# USTREDNA.net
KiCad netlist of a schematic drawn in EAGLE
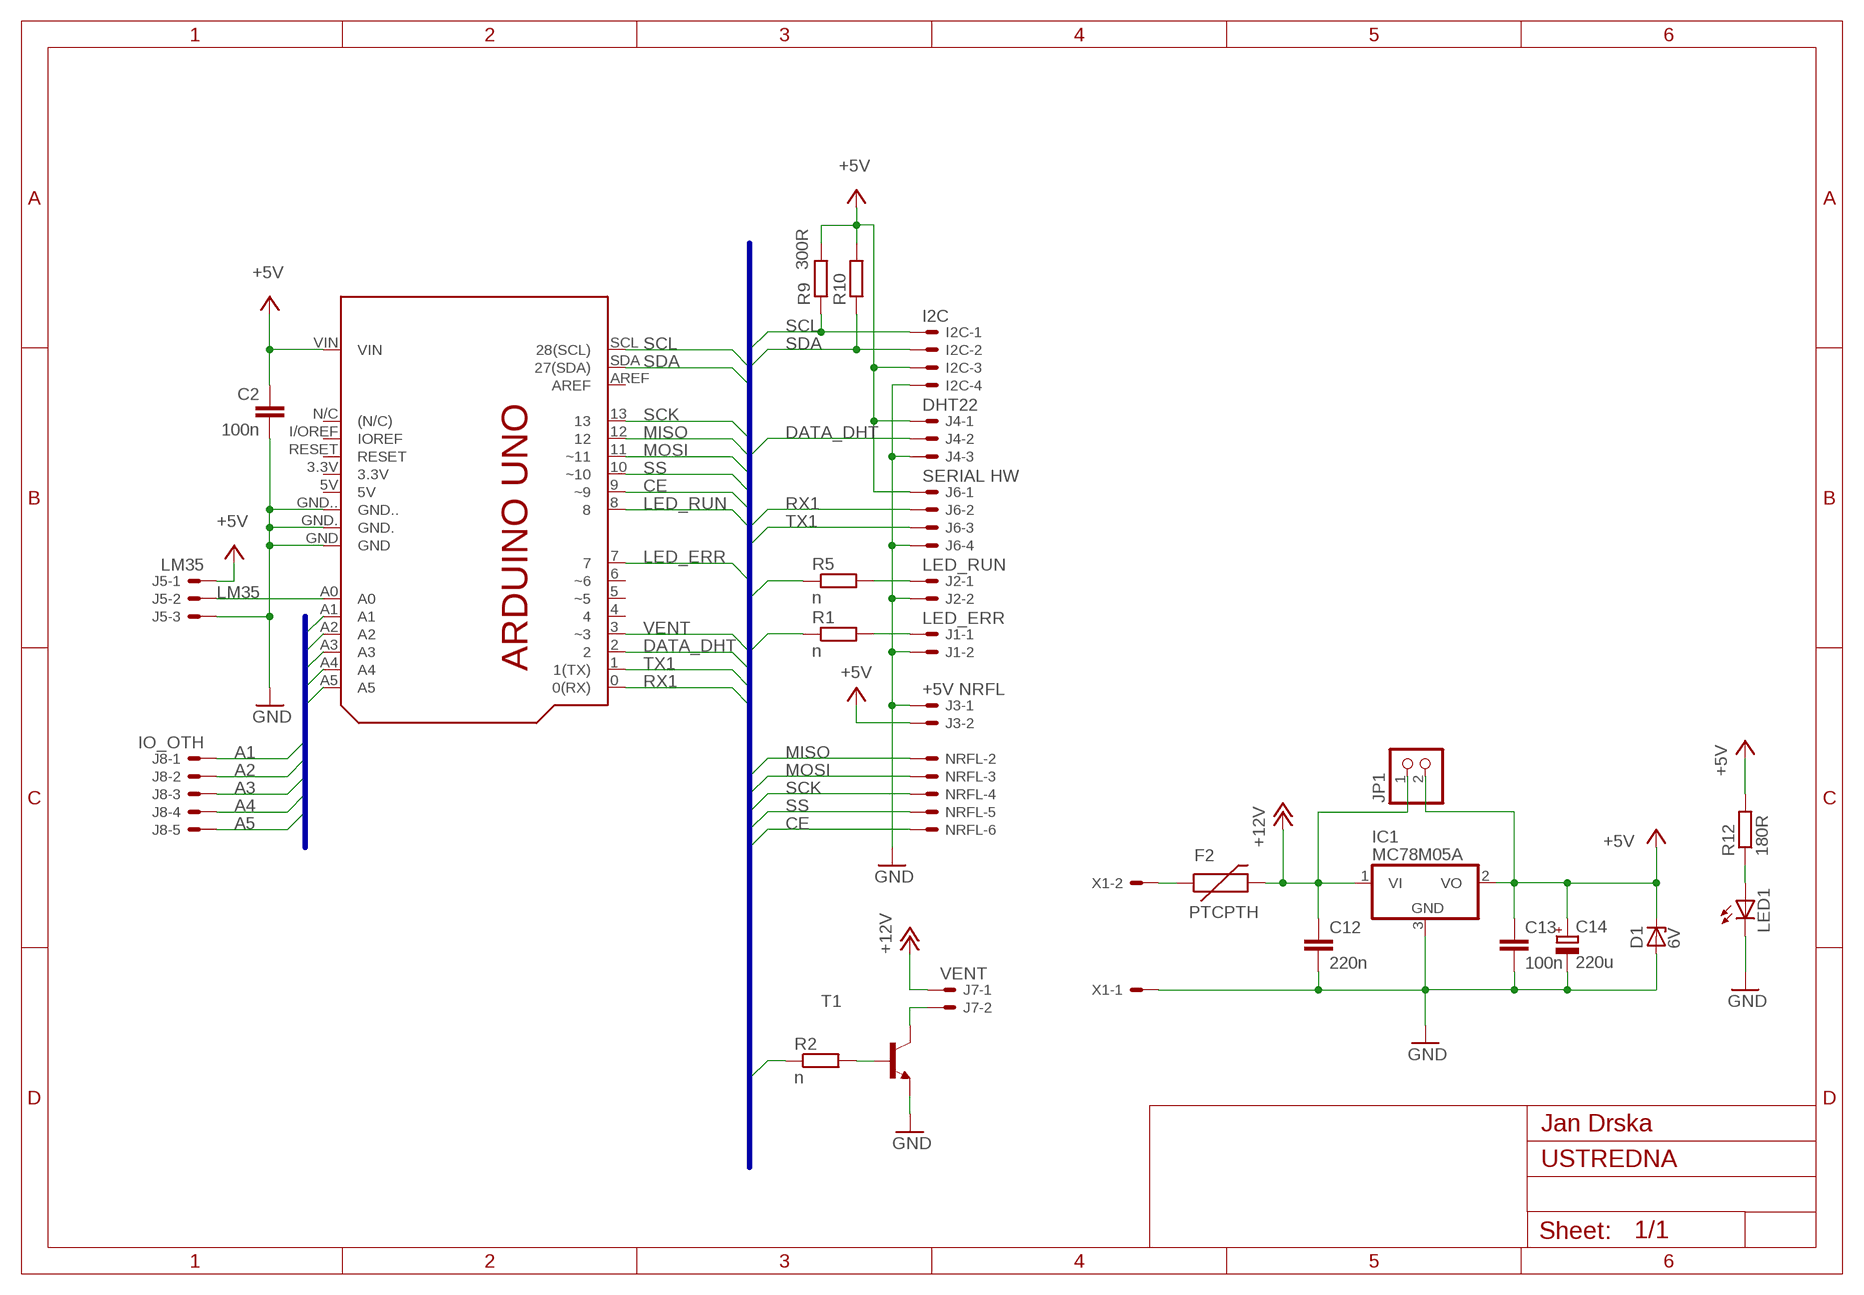
[diagram p0: schematic, sheet 1]

(export (version "E")
  (design (tool "Eeschema 10.0.6"))
  (components
    (comp (ref "C2")
      (value "100n")
      (footprint "eagle-import:C0603")
      (libsource (lib "eagle-import") (part "C-EUC0603"))
    )
    (comp (ref "C12")
      (value "220n")
      (footprint "eagle-import:C0603")
      (libsource (lib "eagle-import") (part "C-EUC0603"))
    )
    (comp (ref "C13")
      (value "100n")
      (footprint "eagle-import:C0603")
      (libsource (lib "eagle-import") (part "C-EUC0603"))
    )
    (comp (ref "C14")
      (value "220u")
      (footprint "eagle-import:E2,5-6E")
      (libsource (lib "eagle-import") (part "CPOL-EUE2,5-6E"))
    )
    (comp (ref "D1")
      (value "6V")
      (footprint "eagle-import:SMB")
      (libsource (lib "eagle-import") (part "ZENER-DIODESMB"))
    )
    (comp (ref "F2")
      (value "PTCPTH")
      (footprint "eagle-import:PTC")
      (libsource (lib "eagle-import") (part "PTCPTH"))
    )
    (comp (ref "I2C")
      (value "I2C")
      (footprint "eagle-import:6410-04")
      (libsource (lib "eagle-import") (part "22-?-0427-2041"))
    )
    (comp (ref "IC1")
      (value "MC78M05A")
      (footprint "eagle-import:TO252")
      (libsource (lib "eagle-import") (part "78DT08"))
    )
    (comp (ref "J1")
      (value "LED_ERR")
      (footprint "eagle-import:6410-02")
      (libsource (lib "eagle-import") (part "22-?-0227-2021"))
    )
    (comp (ref "J2")
      (value "LED_RUN")
      (footprint "eagle-import:6410-02")
      (libsource (lib "eagle-import") (part "22-?-0227-2021"))
    )
    (comp (ref "J3")
      (value "+5V NRFL")
      (footprint "eagle-import:6410-02")
      (libsource (lib "eagle-import") (part "22-?-0227-2021"))
    )
    (comp (ref "J4")
      (value "DHT22")
      (footprint "eagle-import:6410-03")
      (libsource (lib "eagle-import") (part "22-?-0327-2031"))
    )
    (comp (ref "J5")
      (value "LM35")
      (footprint "eagle-import:6410-03")
      (libsource (lib "eagle-import") (part "22-?-0327-2031"))
    )
    (comp (ref "J6")
      (value "SERIAL HW")
      (footprint "eagle-import:6410-04")
      (libsource (lib "eagle-import") (part "22-?-0427-2041"))
    )
    (comp (ref "J7")
      (value "VENT")
      (footprint "eagle-import:6410-02")
      (libsource (lib "eagle-import") (part "22-?-0227-2021"))
    )
    (comp (ref "J8")
      (value "IO_OTH")
      (footprint "eagle-import:6410-05")
      (libsource (lib "eagle-import") (part "22-?-0527-2051"))
    )
    (comp (ref "JP1")
      (value "PINHD-1X2")
      (footprint "eagle-import:1X02")
      (libsource (lib "eagle-import") (part "PINHD-1X2"))
    )
    (comp (ref "LED1")
      (value "LEDCHIP-LED0603")
      (footprint "eagle-import:CHIP-LED0603")
      (libsource (lib "eagle-import") (part "LEDCHIP-LED0603"))
    )
    (comp (ref "NRFL")
      (value "NRFL")
      (footprint "eagle-import:6410-06")
      (libsource (lib "eagle-import") (part "22-?-0627-2061"))
    )
    (comp (ref "PCB1")
      (value "ARDUINO_UNO")
      (footprint "eagle-import:ARDUINO_UNO")
      (libsource (lib "eagle-import") (part "ARDUINO_UNO"))
    )
    (comp (ref "R1")
      (value "n")
      (footprint "eagle-import:R0603")
      (libsource (lib "eagle-import") (part "R-EU_R0603"))
    )
    (comp (ref "R2")
      (value "n")
      (footprint "eagle-import:R0603")
      (libsource (lib "eagle-import") (part "R-EU_R0603"))
    )
    (comp (ref "R5")
      (value "n")
      (footprint "eagle-import:R0603")
      (libsource (lib "eagle-import") (part "R-EU_R0603"))
    )
    (comp (ref "R9")
      (value "R-EU_R0603")
      (footprint "eagle-import:R0603")
      (libsource (lib "eagle-import") (part "R-EU_R0603"))
    )
    (comp (ref "R10")
      (value "300R")
      (footprint "eagle-import:R0603")
      (libsource (lib "eagle-import") (part "R-EU_R0603"))
    )
    (comp (ref "R12")
      (value "180R")
      (footprint "eagle-import:R0603")
      (libsource (lib "eagle-import") (part "R-EU_R0603"))
    )
    (comp (ref "T1")
      (value "-NPN-SOT223")
      (footprint "eagle-import:SOT223")
      (libsource (lib "eagle-import") (part "-NPN-SOT223"))
    )
    (comp (ref "X1")
      (value "22-23-2021")
      (footprint "eagle-import:22-23-2021")
      (fields (field (name "MF") "MOLEX"))
      (libsource (lib "eagle-import") (part "22-23-2021"))
    )
  )
  (nets
    (net (code "1") (name "+5V") (class "Default")
      (node (ref "C13") (pin "1") (pinfunction "1_1") (pintype "passive"))
      (node (ref "C14") (pin "+") (pinfunction "+_+") (pintype "passive"))
      (node (ref "C2") (pin "1") (pinfunction "1_1") (pintype "passive"))
      (node (ref "D1") (pin "C") (pinfunction "C_C") (pintype "passive"))
      (node (ref "I2C") (pin "3") (pinfunction "S_3") (pintype "passive"))
      (node (ref "IC1") (pin "2") (pinfunction "VO_2") (pintype "passive"))
      (node (ref "J3") (pin "2") (pinfunction "S_2") (pintype "passive"))
      (node (ref "J4") (pin "1") (pinfunction "S_1") (pintype "passive"))
      (node (ref "J5") (pin "1") (pinfunction "S_1") (pintype "passive"))
      (node (ref "J6") (pin "1") (pinfunction "S_1") (pintype "passive"))
      (node (ref "JP1") (pin "2") (pinfunction "2_2") (pintype "passive"))
      (node (ref "PCB1") (pin "VIN") (pinfunction "VIN_VIN") (pintype "bidirectional"))
      (node (ref "R10") (pin "2") (pinfunction "2_2") (pintype "passive"))
      (node (ref "R12") (pin "2") (pinfunction "2_2") (pintype "passive"))
      (node (ref "R9") (pin "2") (pinfunction "2_2") (pintype "passive"))
    )
    (net (code "2") (name "+12V") (class "Default")
      (node (ref "C12") (pin "1") (pinfunction "1_1") (pintype "passive"))
      (node (ref "F2") (pin "P$2") (pinfunction "2_P$2") (pintype "bidirectional"))
      (node (ref "IC1") (pin "1") (pinfunction "VI_1") (pintype "input"))
      (node (ref "J7") (pin "1") (pinfunction "S_1") (pintype "passive"))
      (node (ref "JP1") (pin "1") (pinfunction "1_1") (pintype "passive"))
    )
    (net (code "3") (name "/A1") (class "Default")
      (node (ref "J8") (pin "1") (pinfunction "S_1") (pintype "passive"))
      (node (ref "PCB1") (pin "A1") (pinfunction "A1_A1") (pintype "bidirectional"))
    )
    (net (code "4") (name "/A2") (class "Default")
      (node (ref "J8") (pin "2") (pinfunction "S_2") (pintype "passive"))
      (node (ref "PCB1") (pin "A2") (pinfunction "A2_A2") (pintype "bidirectional"))
    )
    (net (code "5") (name "/A3") (class "Default")
      (node (ref "J8") (pin "3") (pinfunction "S_3") (pintype "passive"))
      (node (ref "PCB1") (pin "A3") (pinfunction "A3_A3") (pintype "bidirectional"))
    )
    (net (code "6") (name "/A4") (class "Default")
      (node (ref "J8") (pin "4") (pinfunction "S_4") (pintype "passive"))
      (node (ref "PCB1") (pin "A4") (pinfunction "A4_A4") (pintype "bidirectional"))
    )
    (net (code "7") (name "/A5") (class "Default")
      (node (ref "J8") (pin "5") (pinfunction "S_5") (pintype "passive"))
      (node (ref "PCB1") (pin "A5") (pinfunction "A5_A5") (pintype "bidirectional"))
    )
    (net (code "8") (name "/CE") (class "Default")
      (node (ref "NRFL") (pin "6") (pinfunction "S_6") (pintype "passive"))
      (node (ref "PCB1") (pin "9") (pinfunction "~{9}_9") (pintype "bidirectional"))
    )
    (net (code "9") (name "/DATA_DHT") (class "Default")
      (node (ref "J4") (pin "2") (pinfunction "S_2") (pintype "passive"))
      (node (ref "PCB1") (pin "2") (pinfunction "2_2") (pintype "bidirectional"))
    )
    (net (code "10") (name "/LED_ERR") (class "Default")
      (node (ref "PCB1") (pin "7") (pinfunction "7_7") (pintype "bidirectional"))
      (node (ref "R1") (pin "1") (pinfunction "1_1") (pintype "passive"))
    )
    (net (code "11") (name "/LED_RUN") (class "Default")
      (node (ref "PCB1") (pin "8") (pinfunction "8_8") (pintype "bidirectional"))
      (node (ref "R5") (pin "1") (pinfunction "1_1") (pintype "passive"))
    )
    (net (code "12") (name "/LM35") (class "Default")
      (node (ref "J5") (pin "2") (pinfunction "S_2") (pintype "passive"))
      (node (ref "PCB1") (pin "A0") (pinfunction "A0_A0") (pintype "bidirectional"))
    )
    (net (code "13") (name "/MISO") (class "Default")
      (node (ref "NRFL") (pin "2") (pinfunction "S_2") (pintype "passive"))
      (node (ref "PCB1") (pin "12") (pinfunction "12_12") (pintype "bidirectional"))
    )
    (net (code "14") (name "/MOSI") (class "Default")
      (node (ref "NRFL") (pin "3") (pinfunction "S_3") (pintype "passive"))
      (node (ref "PCB1") (pin "11") (pinfunction "~{11}_11") (pintype "bidirectional"))
    )
    (net (code "15") (name "/RX1") (class "Default")
      (node (ref "J6") (pin "2") (pinfunction "S_2") (pintype "passive"))
      (node (ref "PCB1") (pin "0") (pinfunction "0(RX)_0") (pintype "bidirectional"))
    )
    (net (code "16") (name "/SCK") (class "Default")
      (node (ref "NRFL") (pin "4") (pinfunction "S_4") (pintype "passive"))
      (node (ref "PCB1") (pin "13") (pinfunction "13_13") (pintype "bidirectional"))
    )
    (net (code "17") (name "/SCL") (class "Default")
      (node (ref "I2C") (pin "1") (pinfunction "S_1") (pintype "passive"))
      (node (ref "PCB1") (pin "SCL") (pinfunction "28(SCL)_SCL") (pintype "bidirectional"))
      (node (ref "R9") (pin "1") (pinfunction "1_1") (pintype "passive"))
    )
    (net (code "18") (name "/SDA") (class "Default")
      (node (ref "I2C") (pin "2") (pinfunction "S_2") (pintype "passive"))
      (node (ref "PCB1") (pin "SDA") (pinfunction "27(SDA)_SDA") (pintype "bidirectional"))
      (node (ref "R10") (pin "1") (pinfunction "1_1") (pintype "passive"))
    )
    (net (code "19") (name "/SS") (class "Default")
      (node (ref "NRFL") (pin "5") (pinfunction "S_5") (pintype "passive"))
      (node (ref "PCB1") (pin "10") (pinfunction "~{10}_10") (pintype "bidirectional"))
    )
    (net (code "20") (name "/TX1") (class "Default")
      (node (ref "J6") (pin "3") (pinfunction "S_3") (pintype "passive"))
      (node (ref "PCB1") (pin "1") (pinfunction "1(TX)_1") (pintype "bidirectional"))
    )
    (net (code "21") (name "/VENT") (class "Default")
      (node (ref "PCB1") (pin "3") (pinfunction "~{3}_3") (pintype "bidirectional"))
      (node (ref "R2") (pin "1") (pinfunction "1_1") (pintype "passive"))
    )
    (net (code "23") (name "GND") (class "Default")
      (node (ref "C12") (pin "2") (pinfunction "2_2") (pintype "passive"))
      (node (ref "C13") (pin "2") (pinfunction "2_2") (pintype "passive"))
      (node (ref "C14") (pin "-") (pinfunction "-_-") (pintype "passive"))
      (node (ref "C2") (pin "2") (pinfunction "2_2") (pintype "passive"))
      (node (ref "D1") (pin "A") (pinfunction "A_A") (pintype "passive"))
      (node (ref "I2C") (pin "4") (pinfunction "S_4") (pintype "passive"))
      (node (ref "IC1") (pin "3") (pinfunction "GND_3") (pintype "passive"))
      (node (ref "J1") (pin "2") (pinfunction "S_2") (pintype "passive"))
      (node (ref "J2") (pin "2") (pinfunction "S_2") (pintype "passive"))
      (node (ref "J3") (pin "1") (pinfunction "S_1") (pintype "passive"))
      (node (ref "J4") (pin "3") (pinfunction "S_3") (pintype "passive"))
      (node (ref "J5") (pin "3") (pinfunction "S_3") (pintype "passive"))
      (node (ref "J6") (pin "4") (pinfunction "S_4") (pintype "passive"))
      (node (ref "LED1") (pin "C") (pinfunction "C_C") (pintype "passive"))
      (node (ref "PCB1") (pin "GND") (pinfunction "GND_GND") (pintype "bidirectional"))
      (node (ref "PCB1") (pin "GND.") (pinfunction "GND._GND.") (pintype "bidirectional"))
      (node (ref "PCB1") (pin "GND..") (pinfunction "GND.._GND..") (pintype "bidirectional"))
      (node (ref "T1") (pin "3") (pinfunction "E_3") (pintype "passive"))
      (node (ref "X1") (pin "1") (pinfunction "S_1") (pintype "passive"))
    )
    (net (code "24") (name "Net-(F2-1)") (class "Default")
      (node (ref "F2") (pin "P$1") (pinfunction "1_P$1") (pintype "bidirectional"))
      (node (ref "X1") (pin "2") (pinfunction "S_2") (pintype "passive"))
    )
    (net (code "25") (name "Net-(J1A-S)") (class "Default")
      (node (ref "J1") (pin "1") (pinfunction "S_1") (pintype "passive"))
      (node (ref "R1") (pin "2") (pinfunction "2_2") (pintype "passive"))
    )
    (net (code "26") (name "Net-(J2A-S)") (class "Default")
      (node (ref "J2") (pin "1") (pinfunction "S_1") (pintype "passive"))
      (node (ref "R5") (pin "2") (pinfunction "2_2") (pintype "passive"))
    )
    (net (code "27") (name "Net-(J7B-S)") (class "Default")
      (node (ref "J7") (pin "2") (pinfunction "S_2") (pintype "passive"))
      (node (ref "T1") (pin "4") (pinfunction "C_4") (pintype "passive"))
    )
    (net (code "28") (name "Net-(LED1-PadA)") (class "Default")
      (node (ref "LED1") (pin "A") (pinfunction "A_A") (pintype "passive"))
      (node (ref "R12") (pin "1") (pinfunction "1_1") (pintype "passive"))
    )
    (net (code "29") (name "Net-(T1-B)") (class "Default")
      (node (ref "R2") (pin "2") (pinfunction "2_2") (pintype "passive"))
      (node (ref "T1") (pin "1") (pinfunction "B_1") (pintype "passive"))
    )
    (net (code "30") (name "unconnected-(PCB1-(N{slash}C)-PadN{slash}C)") (class "Default")
      (node (ref "PCB1") (pin "N/C") (pinfunction "(N/C)_N/C") (pintype "bidirectional"))
    )
    (net (code "31") (name "unconnected-(PCB1-IOREF-PadI{slash}OREF)") (class "Default")
      (node (ref "PCB1") (pin "I/OREF") (pinfunction "IOREF_I/OREF") (pintype "bidirectional"))
    )
    (net (code "32") (name "unconnected-(PCB1-Pad3.3V)") (class "Default")
      (node (ref "PCB1") (pin "3.3V") (pinfunction "3.3V_3.3V") (pintype "bidirectional"))
    )
    (net (code "33") (name "unconnected-(PCB1-Pad4)") (class "Default")
      (node (ref "PCB1") (pin "4") (pinfunction "4_4") (pintype "bidirectional"))
    )
    (net (code "34") (name "unconnected-(PCB1-Pad5V)") (class "Default")
      (node (ref "PCB1") (pin "5V") (pinfunction "5V_5V") (pintype "bidirectional"))
    )
    (net (code "35") (name "unconnected-(PCB1-PadAREF)") (class "Default")
      (node (ref "PCB1") (pin "AREF") (pinfunction "AREF_AREF") (pintype "bidirectional"))
    )
    (net (code "36") (name "unconnected-(PCB1-PadRESET)") (class "Default")
      (node (ref "PCB1") (pin "RESET") (pinfunction "RESET_RESET") (pintype "bidirectional"))
    )
    (net (code "37") (name "unconnected-(PCB1-~{5}-Pad5)") (class "Default")
      (node (ref "PCB1") (pin "5") (pinfunction "~{5}_5") (pintype "bidirectional"))
    )
    (net (code "38") (name "unconnected-(PCB1-~{6}-Pad6)") (class "Default")
      (node (ref "PCB1") (pin "6") (pinfunction "~{6}_6") (pintype "bidirectional"))
    )
  )
)
